# MMA8452Q_Breakoutv10_zv1_1.net
KiCad netlist of a schematic drawn in Altium Designer
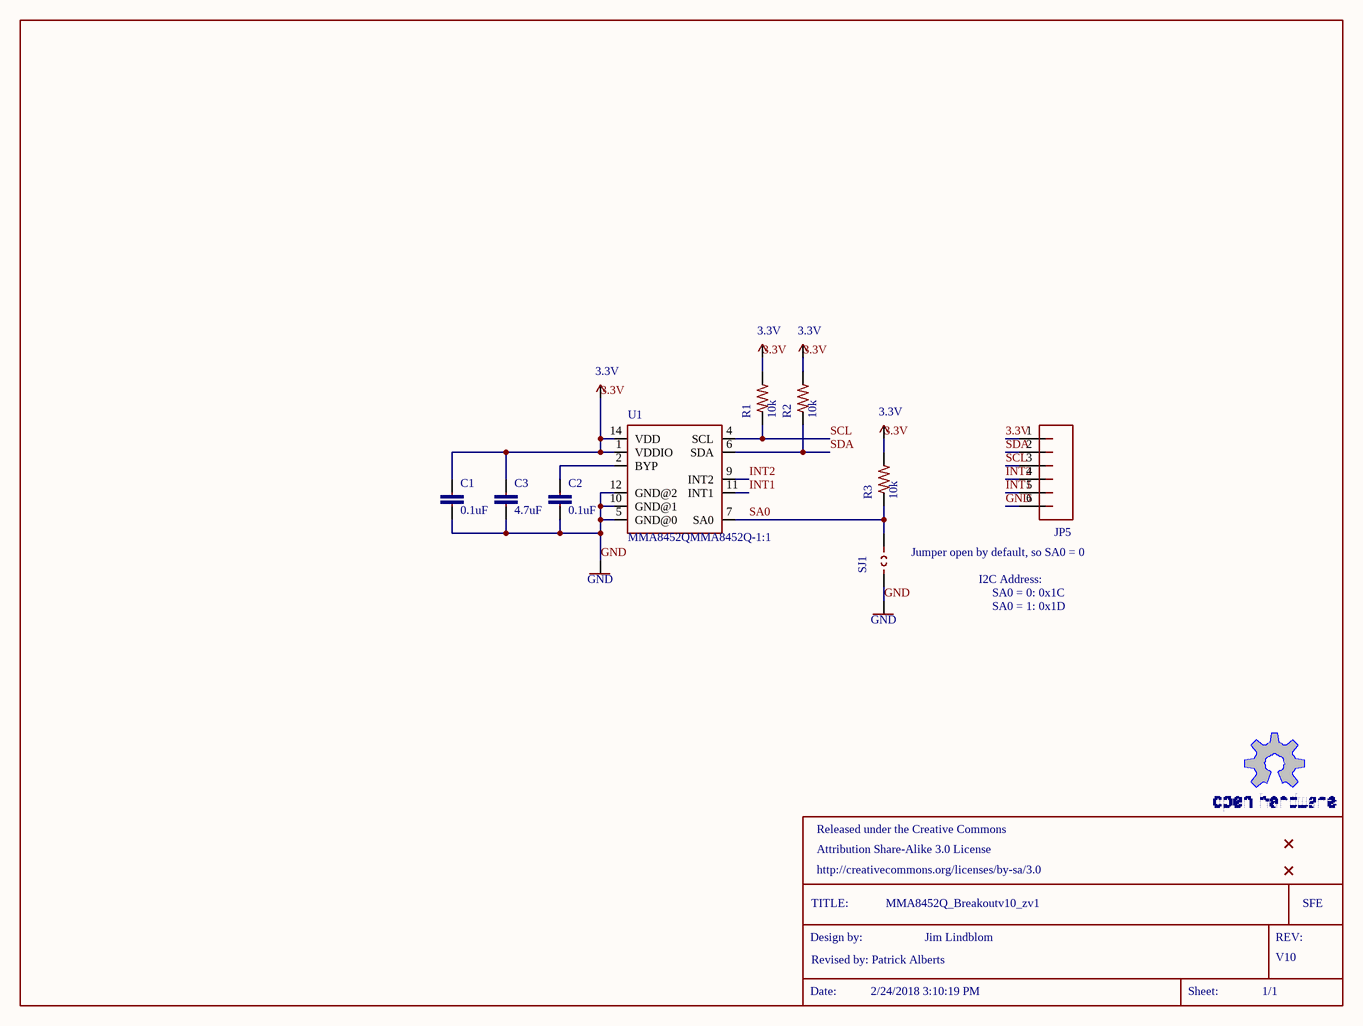
[diagram p0: MMA8452Q_Breakoutv10_zv1_1.SchDoc]

(export (version "E")
  (design (tool "Eeschema 10.0.6"))
  (components
    (comp (ref "C1")
      (value "0.1uF")
      (footprint "0603-CAP")
      (libsource (lib "SparkFun-Capacitors") (part "0.1UF-25V(+80/-20%)(0603)"))
    )
    (comp (ref "C2")
      (value "0.1uF")
      (footprint "0603-CAP")
      (libsource (lib "SparkFun-Capacitors") (part "0.1UF-25V(+80/-20%)(0603)"))
    )
    (comp (ref "C3")
      (value "4.7uF")
      (footprint "0603-CAP")
      (libsource (lib "SparkFun-Capacitors") (part "4.7UF-6.3V-10%(0603)0603"))
    )
    (comp (ref "FID1")
      (value "~")
      (footprint "FIDUCIAL-1X2")
      (libsource (lib "SparkFun-Aesthetics") (part "FIDUCIAL1X2"))
    )
    (comp (ref "FID2")
      (value "~")
      (footprint "FIDUCIAL-1X2")
      (libsource (lib "SparkFun-Aesthetics") (part "FIDUCIAL1X2"))
    )
    (comp (ref "FRAME1")
      (value "~")
      (footprint "CREATIVE_COMMONS")
      (libsource (lib "") (part "FRAME-LETTER_1"))
    )
    (comp (ref "GND1") (value "GND") (libsource (lib "SparkFun") (part "GND")))
    (comp (ref "GND2") (value "GND") (libsource (lib "SparkFun") (part "GND")))
    (comp (ref "JP1")
      (value "~")
      (footprint "SFE-LOGO-FLAME")
      (libsource (lib "SparkFun") (part "LOGO-SFESK"))
    )
    (comp (ref "JP3") (value "~") (footprint "STAND-OFF") (libsource (lib "SparkFun") (part "STAND-OFF")))
    (comp (ref "JP4") (value "~") (footprint "STAND-OFF") (libsource (lib "SparkFun") (part "STAND-OFF")))
    (comp (ref "JP5") (value "~") (footprint "1X06") (libsource (lib "SparkFun") (part "M06SIP")))
    (comp (ref "P+1") (value "3.3V") (libsource (lib "SparkFun") (part "3.3V")))
    (comp (ref "P+2") (value "3.3V") (libsource (lib "SparkFun") (part "3.3V")))
    (comp (ref "P+3") (value "3.3V") (libsource (lib "SparkFun") (part "3.3V")))
    (comp (ref "P+4") (value "3.3V") (libsource (lib "SparkFun") (part "3.3V")))
    (comp (ref "R1")
      (value "10k")
      (footprint "0603-RES")
      (libsource (lib "SparkFun-Resistors") (part "10K-1%RES-00824"))
    )
    (comp (ref "R2")
      (value "10k")
      (footprint "0603-RES")
      (libsource (lib "SparkFun-Resistors") (part "10K-1%RES-00824"))
    )
    (comp (ref "R3")
      (value "10k")
      (footprint "0603-RES")
      (libsource (lib "SparkFun-Resistors") (part "10K-1%RES-00824"))
    )
    (comp (ref "SJ1") (value "~") (footprint "SJ_2S-NO") (libsource (lib "SparkFun") (part "SOLDERJUMPERNO")))
    (comp (ref "U$1") (value "~") (footprint "OSHW-LOGO-S") (libsource (lib "SparkFun") (part "OSHW-LOGOS")))
    (comp (ref "U1")
      (value "MMA8452QMMA8452Q-1:1")
      (footprint "MMA8452Q-1:1")
      (libsource (lib "SparkFun-Sensors") (part "MMA8452QMMA8452Q-1{colon}1"))
    )
  )
  (nets
    (net (code "1") (name "/3.3V") (class "Default")
      (node (ref "C1") (pin "1") (pinfunction "1_1") (pintype "passive"))
      (node (ref "C3") (pin "1") (pinfunction "1_1") (pintype "passive"))
      (node (ref "JP5") (pin "1") (pinfunction "1_1") (pintype "passive"))
      (node (ref "P+1") (pin "0") (pinfunction "3.3V_0") (pintype "passive"))
      (node (ref "P+2") (pin "0") (pinfunction "3.3V_0") (pintype "passive"))
      (node (ref "P+3") (pin "0") (pinfunction "3.3V_0") (pintype "passive"))
      (node (ref "P+4") (pin "0") (pinfunction "3.3V_0") (pintype "passive"))
      (node (ref "R1") (pin "2") (pinfunction "2_2") (pintype "passive"))
      (node (ref "R2") (pin "2") (pinfunction "2_2") (pintype "passive"))
      (node (ref "R3") (pin "2") (pinfunction "2_2") (pintype "passive"))
      (node (ref "U1") (pin "1") (pinfunction "VDDIO_1") (pintype "passive"))
      (node (ref "U1") (pin "14") (pinfunction "VDD_14") (pintype "passive"))
    )
    (net (code "2") (name "/GND") (class "Default")
      (node (ref "C1") (pin "2") (pinfunction "2_2") (pintype "passive"))
      (node (ref "C2") (pin "2") (pinfunction "2_2") (pintype "passive"))
      (node (ref "C3") (pin "2") (pinfunction "2_2") (pintype "passive"))
      (node (ref "GND1") (pin "0") (pinfunction "GND_0") (pintype "passive"))
      (node (ref "GND2") (pin "0") (pinfunction "GND_0") (pintype "passive"))
      (node (ref "JP5") (pin "6") (pinfunction "6_6") (pintype "passive"))
      (node (ref "SJ1") (pin "1") (pinfunction "1_1") (pintype "passive"))
      (node (ref "U1") (pin "10") (pinfunction "GND@1_10") (pintype "passive"))
      (node (ref "U1") (pin "12") (pinfunction "GND@2_12") (pintype "passive"))
      (node (ref "U1") (pin "5") (pinfunction "GND@0_5") (pintype "passive"))
    )
    (net (code "3") (name "/INT1") (class "Default")
      (node (ref "JP5") (pin "5") (pinfunction "5_5") (pintype "passive"))
      (node (ref "U1") (pin "11") (pinfunction "INT1_11") (pintype "passive"))
    )
    (net (code "4") (name "/INT2") (class "Default")
      (node (ref "JP5") (pin "4") (pinfunction "4_4") (pintype "passive"))
      (node (ref "U1") (pin "9") (pinfunction "INT2_9") (pintype "passive"))
    )
    (net (code "5") (name "/SA0") (class "Default")
      (node (ref "R3") (pin "1") (pinfunction "1_1") (pintype "passive"))
      (node (ref "SJ1") (pin "2") (pinfunction "2_2") (pintype "passive"))
      (node (ref "U1") (pin "7") (pinfunction "SA0_7") (pintype "passive"))
    )
    (net (code "6") (name "/SCL") (class "Default")
      (node (ref "JP5") (pin "3") (pinfunction "3_3") (pintype "passive"))
      (node (ref "R1") (pin "1") (pinfunction "1_1") (pintype "passive"))
      (node (ref "U1") (pin "4") (pinfunction "SCL_4") (pintype "passive"))
    )
    (net (code "7") (name "/SDA") (class "Default")
      (node (ref "JP5") (pin "2") (pinfunction "2_2") (pintype "passive"))
      (node (ref "R2") (pin "1") (pinfunction "1_1") (pintype "passive"))
      (node (ref "U1") (pin "6") (pinfunction "SDA_6") (pintype "passive"))
    )
    (net (code "8") (name "Net-(U1-BYP)") (class "Default")
      (node (ref "C2") (pin "1") (pinfunction "1_1") (pintype "passive"))
      (node (ref "U1") (pin "2") (pinfunction "BYP_2") (pintype "passive"))
    )
  )
)
